# Digital_IO_Protection.net
KiCad netlist of a schematic drawn in Altium Designer
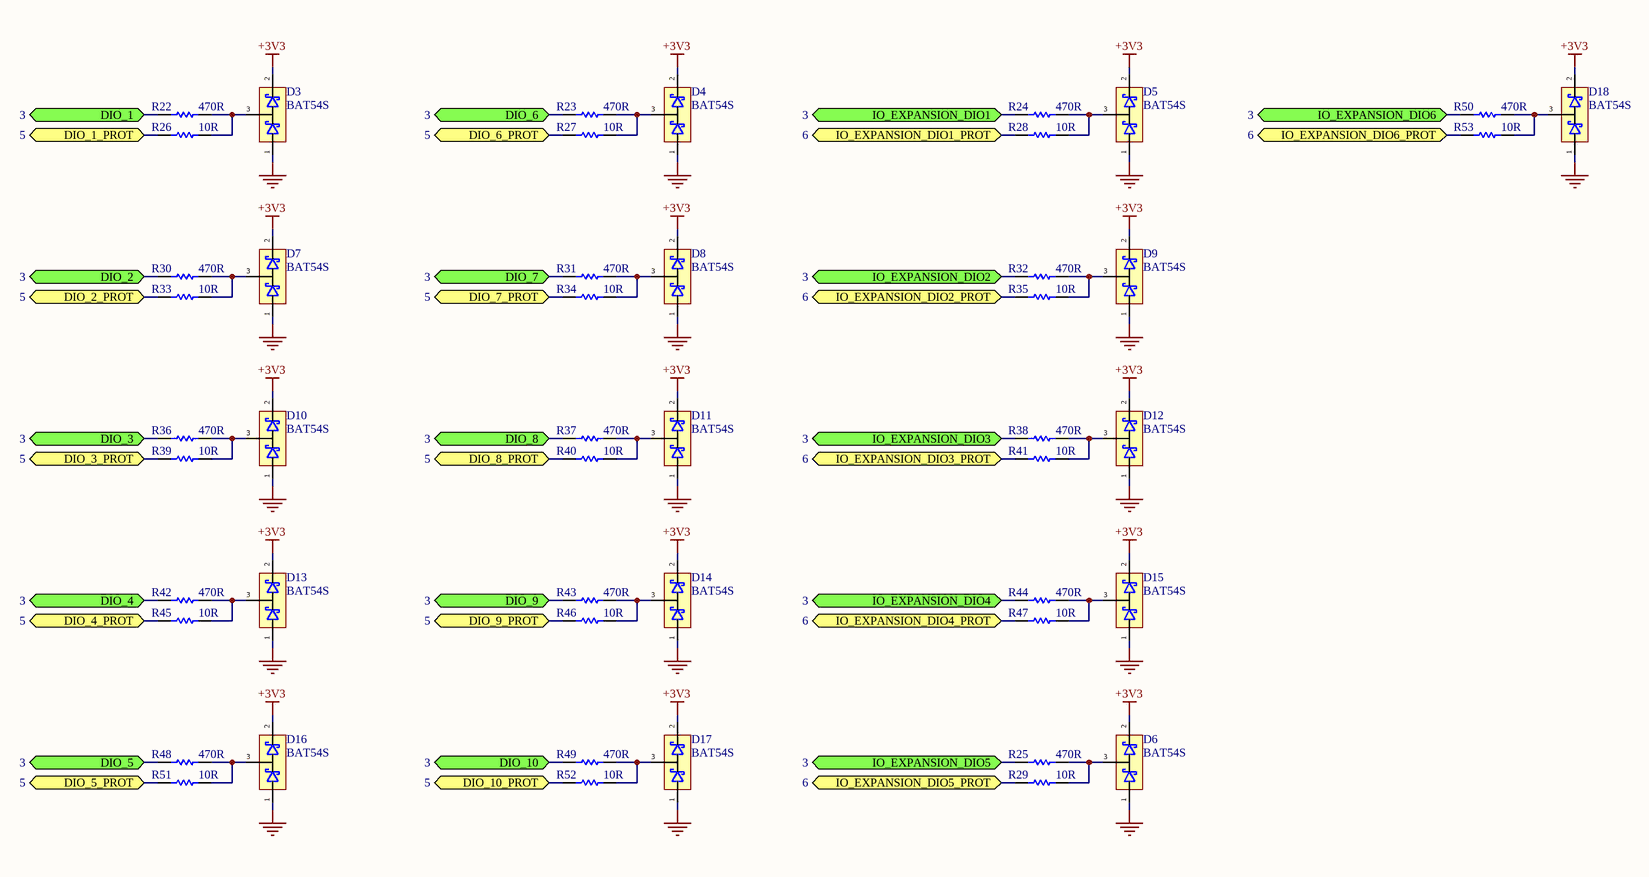
[diagram p0: Digital IO Protection.SchDoc]

(export (version "E")
  (design (tool "Eeschema 10.0.6"))
  (components
    (comp (ref "D3")
      (value "BAT54S")
      (footprint "SOT23-3")
      (description "Rectifier Diode Small Signal Schottky 40V 0.3A 5ns 3-Pin SOT-23 T/R")
      (fields
        (field (name "MANUFACTURER") "STMicroelectronics")
        (field (name "MANUFACTURER PART NUMBER") "BAT54SFILM")
      )
      (libsource (lib "MRT SCH Library") (part "Schottky Diode Array BAT54S"))
    )
    (comp (ref "D4")
      (value "BAT54S")
      (footprint "SOT23-3")
      (description "Rectifier Diode Small Signal Schottky 40V 0.3A 5ns 3-Pin SOT-23 T/R")
      (fields
        (field (name "MANUFACTURER") "STMicroelectronics")
        (field (name "MANUFACTURER PART NUMBER") "BAT54SFILM")
      )
      (libsource (lib "MRT SCH Library") (part "Schottky Diode Array BAT54S"))
    )
    (comp (ref "D5")
      (value "BAT54S")
      (footprint "SOT23-3")
      (description "Rectifier Diode Small Signal Schottky 40V 0.3A 5ns 3-Pin SOT-23 T/R")
      (fields
        (field (name "MANUFACTURER") "STMicroelectronics")
        (field (name "MANUFACTURER PART NUMBER") "BAT54SFILM")
      )
      (libsource (lib "MRT SCH Library") (part "Schottky Diode Array BAT54S"))
    )
    (comp (ref "D6")
      (value "BAT54S")
      (footprint "SOT23-3")
      (description "Rectifier Diode Small Signal Schottky 40V 0.3A 5ns 3-Pin SOT-23 T/R")
      (fields
        (field (name "MANUFACTURER") "STMicroelectronics")
        (field (name "MANUFACTURER PART NUMBER") "BAT54SFILM")
      )
      (libsource (lib "MRT SCH Library") (part "Schottky Diode Array BAT54S"))
    )
    (comp (ref "D7")
      (value "BAT54S")
      (footprint "SOT23-3")
      (description "Rectifier Diode Small Signal Schottky 40V 0.3A 5ns 3-Pin SOT-23 T/R")
      (fields
        (field (name "MANUFACTURER") "STMicroelectronics")
        (field (name "MANUFACTURER PART NUMBER") "BAT54SFILM")
      )
      (libsource (lib "MRT SCH Library") (part "Schottky Diode Array BAT54S"))
    )
    (comp (ref "D8")
      (value "BAT54S")
      (footprint "SOT23-3")
      (description "Rectifier Diode Small Signal Schottky 40V 0.3A 5ns 3-Pin SOT-23 T/R")
      (fields
        (field (name "MANUFACTURER") "STMicroelectronics")
        (field (name "MANUFACTURER PART NUMBER") "BAT54SFILM")
      )
      (libsource (lib "MRT SCH Library") (part "Schottky Diode Array BAT54S"))
    )
    (comp (ref "D9")
      (value "BAT54S")
      (footprint "SOT23-3")
      (description "Rectifier Diode Small Signal Schottky 40V 0.3A 5ns 3-Pin SOT-23 T/R")
      (fields
        (field (name "MANUFACTURER") "STMicroelectronics")
        (field (name "MANUFACTURER PART NUMBER") "BAT54SFILM")
      )
      (libsource (lib "MRT SCH Library") (part "Schottky Diode Array BAT54S"))
    )
    (comp (ref "D10")
      (value "BAT54S")
      (footprint "SOT23-3")
      (description "Rectifier Diode Small Signal Schottky 40V 0.3A 5ns 3-Pin SOT-23 T/R")
      (fields
        (field (name "MANUFACTURER") "STMicroelectronics")
        (field (name "MANUFACTURER PART NUMBER") "BAT54SFILM")
      )
      (libsource (lib "MRT SCH Library") (part "Schottky Diode Array BAT54S"))
    )
    (comp (ref "D11")
      (value "BAT54S")
      (footprint "SOT23-3")
      (description "Rectifier Diode Small Signal Schottky 40V 0.3A 5ns 3-Pin SOT-23 T/R")
      (fields
        (field (name "MANUFACTURER") "STMicroelectronics")
        (field (name "MANUFACTURER PART NUMBER") "BAT54SFILM")
      )
      (libsource (lib "MRT SCH Library") (part "Schottky Diode Array BAT54S"))
    )
    (comp (ref "D12")
      (value "BAT54S")
      (footprint "SOT23-3")
      (description "Rectifier Diode Small Signal Schottky 40V 0.3A 5ns 3-Pin SOT-23 T/R")
      (fields
        (field (name "MANUFACTURER") "STMicroelectronics")
        (field (name "MANUFACTURER PART NUMBER") "BAT54SFILM")
      )
      (libsource (lib "MRT SCH Library") (part "Schottky Diode Array BAT54S"))
    )
    (comp (ref "D13")
      (value "BAT54S")
      (footprint "SOT23-3")
      (description "Rectifier Diode Small Signal Schottky 40V 0.3A 5ns 3-Pin SOT-23 T/R")
      (fields
        (field (name "MANUFACTURER") "STMicroelectronics")
        (field (name "MANUFACTURER PART NUMBER") "BAT54SFILM")
      )
      (libsource (lib "MRT SCH Library") (part "Schottky Diode Array BAT54S"))
    )
    (comp (ref "D14")
      (value "BAT54S")
      (footprint "SOT23-3")
      (description "Rectifier Diode Small Signal Schottky 40V 0.3A 5ns 3-Pin SOT-23 T/R")
      (fields
        (field (name "MANUFACTURER") "STMicroelectronics")
        (field (name "MANUFACTURER PART NUMBER") "BAT54SFILM")
      )
      (libsource (lib "MRT SCH Library") (part "Schottky Diode Array BAT54S"))
    )
    (comp (ref "D15")
      (value "BAT54S")
      (footprint "SOT23-3")
      (description "Rectifier Diode Small Signal Schottky 40V 0.3A 5ns 3-Pin SOT-23 T/R")
      (fields
        (field (name "MANUFACTURER") "STMicroelectronics")
        (field (name "MANUFACTURER PART NUMBER") "BAT54SFILM")
      )
      (libsource (lib "MRT SCH Library") (part "Schottky Diode Array BAT54S"))
    )
    (comp (ref "D16")
      (value "BAT54S")
      (footprint "SOT23-3")
      (description "Rectifier Diode Small Signal Schottky 40V 0.3A 5ns 3-Pin SOT-23 T/R")
      (fields
        (field (name "MANUFACTURER") "STMicroelectronics")
        (field (name "MANUFACTURER PART NUMBER") "BAT54SFILM")
      )
      (libsource (lib "MRT SCH Library") (part "Schottky Diode Array BAT54S"))
    )
    (comp (ref "D17")
      (value "BAT54S")
      (footprint "SOT23-3")
      (description "Rectifier Diode Small Signal Schottky 40V 0.3A 5ns 3-Pin SOT-23 T/R")
      (fields
        (field (name "MANUFACTURER") "STMicroelectronics")
        (field (name "MANUFACTURER PART NUMBER") "BAT54SFILM")
      )
      (libsource (lib "MRT SCH Library") (part "Schottky Diode Array BAT54S"))
    )
    (comp (ref "D18")
      (value "BAT54S")
      (footprint "SOT23-3")
      (description "Rectifier Diode Small Signal Schottky 40V 0.3A 5ns 3-Pin SOT-23 T/R")
      (fields
        (field (name "MANUFACTURER") "STMicroelectronics")
        (field (name "MANUFACTURER PART NUMBER") "BAT54SFILM")
      )
      (libsource (lib "MRT SCH Library") (part "Schottky Diode Array BAT54S"))
    )
    (comp (ref "R22")
      (value "470R")
      (footprint "0805 RES")
      (fields (field (name "PUBLISHER") "Altium Limited"))
      (libsource (lib "Miscellaneous Devices") (part "Res1"))
    )
    (comp (ref "R23")
      (value "470R")
      (footprint "0805 RES")
      (fields (field (name "PUBLISHER") "Altium Limited"))
      (libsource (lib "Miscellaneous Devices") (part "Res1"))
    )
    (comp (ref "R24")
      (value "470R")
      (footprint "0805 RES")
      (fields (field (name "PUBLISHER") "Altium Limited"))
      (libsource (lib "Miscellaneous Devices") (part "Res1"))
    )
    (comp (ref "R25")
      (value "470R")
      (footprint "0805 RES")
      (fields (field (name "PUBLISHER") "Altium Limited"))
      (libsource (lib "Miscellaneous Devices") (part "Res1"))
    )
    (comp (ref "R26")
      (value "10R")
      (footprint "0603 RES")
      (fields (field (name "PUBLISHER") "Altium Limited"))
      (libsource (lib "Miscellaneous Devices") (part "Res1"))
    )
    (comp (ref "R27")
      (value "10R")
      (footprint "0603 RES")
      (fields (field (name "PUBLISHER") "Altium Limited"))
      (libsource (lib "Miscellaneous Devices") (part "Res1"))
    )
    (comp (ref "R28")
      (value "10R")
      (footprint "0603 RES")
      (fields (field (name "PUBLISHER") "Altium Limited"))
      (libsource (lib "Miscellaneous Devices") (part "Res1"))
    )
    (comp (ref "R29")
      (value "10R")
      (footprint "0603 RES")
      (fields (field (name "PUBLISHER") "Altium Limited"))
      (libsource (lib "Miscellaneous Devices") (part "Res1"))
    )
    (comp (ref "R30")
      (value "470R")
      (footprint "0805 RES")
      (fields (field (name "PUBLISHER") "Altium Limited"))
      (libsource (lib "Miscellaneous Devices") (part "Res1"))
    )
    (comp (ref "R31")
      (value "470R")
      (footprint "0805 RES")
      (fields (field (name "PUBLISHER") "Altium Limited"))
      (libsource (lib "Miscellaneous Devices") (part "Res1"))
    )
    (comp (ref "R32")
      (value "470R")
      (footprint "0805 RES")
      (fields (field (name "PUBLISHER") "Altium Limited"))
      (libsource (lib "Miscellaneous Devices") (part "Res1"))
    )
    (comp (ref "R33")
      (value "10R")
      (footprint "0603 RES")
      (fields (field (name "PUBLISHER") "Altium Limited"))
      (libsource (lib "Miscellaneous Devices") (part "Res1"))
    )
    (comp (ref "R34")
      (value "10R")
      (footprint "0603 RES")
      (fields (field (name "PUBLISHER") "Altium Limited"))
      (libsource (lib "Miscellaneous Devices") (part "Res1"))
    )
    (comp (ref "R35")
      (value "10R")
      (footprint "0603 RES")
      (fields (field (name "PUBLISHER") "Altium Limited"))
      (libsource (lib "Miscellaneous Devices") (part "Res1"))
    )
    (comp (ref "R36")
      (value "470R")
      (footprint "0805 RES")
      (fields (field (name "PUBLISHER") "Altium Limited"))
      (libsource (lib "Miscellaneous Devices") (part "Res1"))
    )
    (comp (ref "R37")
      (value "470R")
      (footprint "0805 RES")
      (fields (field (name "PUBLISHER") "Altium Limited"))
      (libsource (lib "Miscellaneous Devices") (part "Res1"))
    )
    (comp (ref "R38")
      (value "470R")
      (footprint "0805 RES")
      (fields (field (name "PUBLISHER") "Altium Limited"))
      (libsource (lib "Miscellaneous Devices") (part "Res1"))
    )
    (comp (ref "R39")
      (value "10R")
      (footprint "0603 RES")
      (fields (field (name "PUBLISHER") "Altium Limited"))
      (libsource (lib "Miscellaneous Devices") (part "Res1"))
    )
    (comp (ref "R40")
      (value "10R")
      (footprint "0603 RES")
      (fields (field (name "PUBLISHER") "Altium Limited"))
      (libsource (lib "Miscellaneous Devices") (part "Res1"))
    )
    (comp (ref "R41")
      (value "10R")
      (footprint "0603 RES")
      (fields (field (name "PUBLISHER") "Altium Limited"))
      (libsource (lib "Miscellaneous Devices") (part "Res1"))
    )
    (comp (ref "R42")
      (value "470R")
      (footprint "0805 RES")
      (fields (field (name "PUBLISHER") "Altium Limited"))
      (libsource (lib "Miscellaneous Devices") (part "Res1"))
    )
    (comp (ref "R43")
      (value "470R")
      (footprint "0805 RES")
      (fields (field (name "PUBLISHER") "Altium Limited"))
      (libsource (lib "Miscellaneous Devices") (part "Res1"))
    )
    (comp (ref "R44")
      (value "470R")
      (footprint "0805 RES")
      (fields (field (name "PUBLISHER") "Altium Limited"))
      (libsource (lib "Miscellaneous Devices") (part "Res1"))
    )
    (comp (ref "R45")
      (value "10R")
      (footprint "0603 RES")
      (fields (field (name "PUBLISHER") "Altium Limited"))
      (libsource (lib "Miscellaneous Devices") (part "Res1"))
    )
    (comp (ref "R46")
      (value "10R")
      (footprint "0603 RES")
      (fields (field (name "PUBLISHER") "Altium Limited"))
      (libsource (lib "Miscellaneous Devices") (part "Res1"))
    )
    (comp (ref "R47")
      (value "10R")
      (footprint "0603 RES")
      (fields (field (name "PUBLISHER") "Altium Limited"))
      (libsource (lib "Miscellaneous Devices") (part "Res1"))
    )
    (comp (ref "R48")
      (value "470R")
      (footprint "0805 RES")
      (fields (field (name "PUBLISHER") "Altium Limited"))
      (libsource (lib "Miscellaneous Devices") (part "Res1"))
    )
    (comp (ref "R49")
      (value "470R")
      (footprint "0805 RES")
      (fields (field (name "PUBLISHER") "Altium Limited"))
      (libsource (lib "Miscellaneous Devices") (part "Res1"))
    )
    (comp (ref "R50")
      (value "470R")
      (footprint "0805 RES")
      (fields (field (name "PUBLISHER") "Altium Limited"))
      (libsource (lib "Miscellaneous Devices") (part "Res1"))
    )
    (comp (ref "R51")
      (value "10R")
      (footprint "0603 RES")
      (fields (field (name "PUBLISHER") "Altium Limited"))
      (libsource (lib "Miscellaneous Devices") (part "Res1"))
    )
    (comp (ref "R52")
      (value "10R")
      (footprint "0603 RES")
      (fields (field (name "PUBLISHER") "Altium Limited"))
      (libsource (lib "Miscellaneous Devices") (part "Res1"))
    )
    (comp (ref "R53")
      (value "10R")
      (footprint "0603 RES")
      (fields (field (name "PUBLISHER") "Altium Limited"))
      (libsource (lib "Miscellaneous Devices") (part "Res1"))
    )
  )
  (nets
    (net (code "1") (name "+3V3") (class "Default")
      (node (ref "D10") (pin "2") (pinfunction "2_2") (pintype "passive"))
      (node (ref "D11") (pin "2") (pinfunction "2_2") (pintype "passive"))
      (node (ref "D12") (pin "2") (pinfunction "2_2") (pintype "passive"))
      (node (ref "D13") (pin "2") (pinfunction "2_2") (pintype "passive"))
      (node (ref "D14") (pin "2") (pinfunction "2_2") (pintype "passive"))
      (node (ref "D15") (pin "2") (pinfunction "2_2") (pintype "passive"))
      (node (ref "D16") (pin "2") (pinfunction "2_2") (pintype "passive"))
      (node (ref "D17") (pin "2") (pinfunction "2_2") (pintype "passive"))
      (node (ref "D18") (pin "2") (pinfunction "2_2") (pintype "passive"))
      (node (ref "D3") (pin "2") (pinfunction "2_2") (pintype "passive"))
      (node (ref "D4") (pin "2") (pinfunction "2_2") (pintype "passive"))
      (node (ref "D5") (pin "2") (pinfunction "2_2") (pintype "passive"))
      (node (ref "D6") (pin "2") (pinfunction "2_2") (pintype "passive"))
      (node (ref "D7") (pin "2") (pinfunction "2_2") (pintype "passive"))
      (node (ref "D8") (pin "2") (pinfunction "2_2") (pintype "passive"))
      (node (ref "D9") (pin "2") (pinfunction "2_2") (pintype "passive"))
    )
    (net (code "2") (name "/DIO_1") (class "Default")
      (node (ref "R22") (pin "1") (pinfunction "1_1") (pintype "passive"))
    )
    (net (code "3") (name "/DIO_1_PROT") (class "Default")
      (node (ref "R26") (pin "1") (pinfunction "1_1") (pintype "passive"))
    )
    (net (code "4") (name "/DIO_2") (class "Default")
      (node (ref "R30") (pin "1") (pinfunction "1_1") (pintype "passive"))
    )
    (net (code "5") (name "/DIO_2_PROT") (class "Default")
      (node (ref "R33") (pin "1") (pinfunction "1_1") (pintype "passive"))
    )
    (net (code "6") (name "/DIO_3") (class "Default")
      (node (ref "R36") (pin "1") (pinfunction "1_1") (pintype "passive"))
    )
    (net (code "7") (name "/DIO_3_PROT") (class "Default")
      (node (ref "R39") (pin "1") (pinfunction "1_1") (pintype "passive"))
    )
    (net (code "8") (name "/DIO_4") (class "Default")
      (node (ref "R42") (pin "1") (pinfunction "1_1") (pintype "passive"))
    )
    (net (code "9") (name "/DIO_4_PROT") (class "Default")
      (node (ref "R45") (pin "1") (pinfunction "1_1") (pintype "passive"))
    )
    (net (code "10") (name "/DIO_5") (class "Default")
      (node (ref "R48") (pin "1") (pinfunction "1_1") (pintype "passive"))
    )
    (net (code "11") (name "/DIO_5_PROT") (class "Default")
      (node (ref "R51") (pin "1") (pinfunction "1_1") (pintype "passive"))
    )
    (net (code "12") (name "/DIO_6") (class "Default")
      (node (ref "R23") (pin "1") (pinfunction "1_1") (pintype "passive"))
    )
    (net (code "13") (name "/DIO_6_PROT") (class "Default")
      (node (ref "R27") (pin "1") (pinfunction "1_1") (pintype "passive"))
    )
    (net (code "14") (name "/DIO_7") (class "Default")
      (node (ref "R31") (pin "1") (pinfunction "1_1") (pintype "passive"))
    )
    (net (code "15") (name "/DIO_7_PROT") (class "Default")
      (node (ref "R34") (pin "1") (pinfunction "1_1") (pintype "passive"))
    )
    (net (code "16") (name "/DIO_8") (class "Default")
      (node (ref "R37") (pin "1") (pinfunction "1_1") (pintype "passive"))
    )
    (net (code "17") (name "/DIO_8_PROT") (class "Default")
      (node (ref "R40") (pin "1") (pinfunction "1_1") (pintype "passive"))
    )
    (net (code "18") (name "/DIO_9") (class "Default")
      (node (ref "R43") (pin "1") (pinfunction "1_1") (pintype "passive"))
    )
    (net (code "19") (name "/DIO_9_PROT") (class "Default")
      (node (ref "R46") (pin "1") (pinfunction "1_1") (pintype "passive"))
    )
    (net (code "20") (name "/DIO_10") (class "Default")
      (node (ref "R49") (pin "1") (pinfunction "1_1") (pintype "passive"))
    )
    (net (code "21") (name "/DIO_10_PROT") (class "Default")
      (node (ref "R52") (pin "1") (pinfunction "1_1") (pintype "passive"))
    )
    (net (code "22") (name "/IO_EXPANSION_DIO1") (class "Default")
      (node (ref "R24") (pin "1") (pinfunction "1_1") (pintype "passive"))
    )
    (net (code "23") (name "/IO_EXPANSION_DIO1_PROT") (class "Default")
      (node (ref "R28") (pin "1") (pinfunction "1_1") (pintype "passive"))
    )
    (net (code "24") (name "/IO_EXPANSION_DIO2") (class "Default")
      (node (ref "R32") (pin "1") (pinfunction "1_1") (pintype "passive"))
    )
    (net (code "25") (name "/IO_EXPANSION_DIO2_PROT") (class "Default")
      (node (ref "R35") (pin "1") (pinfunction "1_1") (pintype "passive"))
    )
    (net (code "26") (name "/IO_EXPANSION_DIO3") (class "Default")
      (node (ref "R38") (pin "1") (pinfunction "1_1") (pintype "passive"))
    )
    (net (code "27") (name "/IO_EXPANSION_DIO3_PROT") (class "Default")
      (node (ref "R41") (pin "1") (pinfunction "1_1") (pintype "passive"))
    )
    (net (code "28") (name "/IO_EXPANSION_DIO4") (class "Default")
      (node (ref "R44") (pin "1") (pinfunction "1_1") (pintype "passive"))
    )
    (net (code "29") (name "/IO_EXPANSION_DIO4_PROT") (class "Default")
      (node (ref "R47") (pin "1") (pinfunction "1_1") (pintype "passive"))
    )
    (net (code "30") (name "/IO_EXPANSION_DIO5") (class "Default")
      (node (ref "R25") (pin "1") (pinfunction "1_1") (pintype "passive"))
    )
    (net (code "31") (name "/IO_EXPANSION_DIO5_PROT") (class "Default")
      (node (ref "R29") (pin "1") (pinfunction "1_1") (pintype "passive"))
    )
    (net (code "32") (name "/IO_EXPANSION_DIO6") (class "Default")
      (node (ref "R50") (pin "1") (pinfunction "1_1") (pintype "passive"))
    )
    (net (code "33") (name "/IO_EXPANSION_DIO6_PROT") (class "Default")
      (node (ref "R53") (pin "1") (pinfunction "1_1") (pintype "passive"))
    )
    (net (code "34") (name "GND") (class "Default")
      (node (ref "D10") (pin "1") (pinfunction "1_1") (pintype "passive"))
      (node (ref "D11") (pin "1") (pinfunction "1_1") (pintype "passive"))
      (node (ref "D12") (pin "1") (pinfunction "1_1") (pintype "passive"))
      (node (ref "D13") (pin "1") (pinfunction "1_1") (pintype "passive"))
      (node (ref "D14") (pin "1") (pinfunction "1_1") (pintype "passive"))
      (node (ref "D15") (pin "1") (pinfunction "1_1") (pintype "passive"))
      (node (ref "D16") (pin "1") (pinfunction "1_1") (pintype "passive"))
      (node (ref "D17") (pin "1") (pinfunction "1_1") (pintype "passive"))
      (node (ref "D18") (pin "1") (pinfunction "1_1") (pintype "passive"))
      (node (ref "D3") (pin "1") (pinfunction "1_1") (pintype "passive"))
      (node (ref "D4") (pin "1") (pinfunction "1_1") (pintype "passive"))
      (node (ref "D5") (pin "1") (pinfunction "1_1") (pintype "passive"))
      (node (ref "D6") (pin "1") (pinfunction "1_1") (pintype "passive"))
      (node (ref "D7") (pin "1") (pinfunction "1_1") (pintype "passive"))
      (node (ref "D8") (pin "1") (pinfunction "1_1") (pintype "passive"))
      (node (ref "D9") (pin "1") (pinfunction "1_1") (pintype "passive"))
    )
    (net (code "35") (name "Net-(D3-Pad3)") (class "Default")
      (node (ref "D3") (pin "3") (pinfunction "3_3") (pintype "passive"))
      (node (ref "R22") (pin "2") (pinfunction "2_2") (pintype "passive"))
      (node (ref "R26") (pin "2") (pinfunction "2_2") (pintype "passive"))
    )
    (net (code "36") (name "Net-(D4-Pad3)") (class "Default")
      (node (ref "D4") (pin "3") (pinfunction "3_3") (pintype "passive"))
      (node (ref "R23") (pin "2") (pinfunction "2_2") (pintype "passive"))
      (node (ref "R27") (pin "2") (pinfunction "2_2") (pintype "passive"))
    )
    (net (code "37") (name "Net-(D5-Pad3)") (class "Default")
      (node (ref "D5") (pin "3") (pinfunction "3_3") (pintype "passive"))
      (node (ref "R24") (pin "2") (pinfunction "2_2") (pintype "passive"))
      (node (ref "R28") (pin "2") (pinfunction "2_2") (pintype "passive"))
    )
    (net (code "38") (name "Net-(D6-Pad3)") (class "Default")
      (node (ref "D6") (pin "3") (pinfunction "3_3") (pintype "passive"))
      (node (ref "R25") (pin "2") (pinfunction "2_2") (pintype "passive"))
      (node (ref "R29") (pin "2") (pinfunction "2_2") (pintype "passive"))
    )
    (net (code "39") (name "Net-(D7-Pad3)") (class "Default")
      (node (ref "D7") (pin "3") (pinfunction "3_3") (pintype "passive"))
      (node (ref "R30") (pin "2") (pinfunction "2_2") (pintype "passive"))
      (node (ref "R33") (pin "2") (pinfunction "2_2") (pintype "passive"))
    )
    (net (code "40") (name "Net-(D8-Pad3)") (class "Default")
      (node (ref "D8") (pin "3") (pinfunction "3_3") (pintype "passive"))
      (node (ref "R31") (pin "2") (pinfunction "2_2") (pintype "passive"))
      (node (ref "R34") (pin "2") (pinfunction "2_2") (pintype "passive"))
    )
    (net (code "41") (name "Net-(D9-Pad3)") (class "Default")
      (node (ref "D9") (pin "3") (pinfunction "3_3") (pintype "passive"))
      (node (ref "R32") (pin "2") (pinfunction "2_2") (pintype "passive"))
      (node (ref "R35") (pin "2") (pinfunction "2_2") (pintype "passive"))
    )
    (net (code "42") (name "Net-(D10-Pad3)") (class "Default")
      (node (ref "D10") (pin "3") (pinfunction "3_3") (pintype "passive"))
      (node (ref "R36") (pin "2") (pinfunction "2_2") (pintype "passive"))
      (node (ref "R39") (pin "2") (pinfunction "2_2") (pintype "passive"))
    )
    (net (code "43") (name "Net-(D11-Pad3)") (class "Default")
      (node (ref "D11") (pin "3") (pinfunction "3_3") (pintype "passive"))
      (node (ref "R37") (pin "2") (pinfunction "2_2") (pintype "passive"))
      (node (ref "R40") (pin "2") (pinfunction "2_2") (pintype "passive"))
    )
    (net (code "44") (name "Net-(D12-Pad3)") (class "Default")
      (node (ref "D12") (pin "3") (pinfunction "3_3") (pintype "passive"))
      (node (ref "R38") (pin "2") (pinfunction "2_2") (pintype "passive"))
      (node (ref "R41") (pin "2") (pinfunction "2_2") (pintype "passive"))
    )
    (net (code "45") (name "Net-(D13-Pad3)") (class "Default")
      (node (ref "D13") (pin "3") (pinfunction "3_3") (pintype "passive"))
      (node (ref "R42") (pin "2") (pinfunction "2_2") (pintype "passive"))
      (node (ref "R45") (pin "2") (pinfunction "2_2") (pintype "passive"))
    )
    (net (code "46") (name "Net-(D14-Pad3)") (class "Default")
      (node (ref "D14") (pin "3") (pinfunction "3_3") (pintype "passive"))
      (node (ref "R43") (pin "2") (pinfunction "2_2") (pintype "passive"))
      (node (ref "R46") (pin "2") (pinfunction "2_2") (pintype "passive"))
    )
    (net (code "47") (name "Net-(D15-Pad3)") (class "Default")
      (node (ref "D15") (pin "3") (pinfunction "3_3") (pintype "passive"))
      (node (ref "R44") (pin "2") (pinfunction "2_2") (pintype "passive"))
      (node (ref "R47") (pin "2") (pinfunction "2_2") (pintype "passive"))
    )
    (net (code "48") (name "Net-(D16-Pad3)") (class "Default")
      (node (ref "D16") (pin "3") (pinfunction "3_3") (pintype "passive"))
      (node (ref "R48") (pin "2") (pinfunction "2_2") (pintype "passive"))
      (node (ref "R51") (pin "2") (pinfunction "2_2") (pintype "passive"))
    )
    (net (code "49") (name "Net-(D17-Pad3)") (class "Default")
      (node (ref "D17") (pin "3") (pinfunction "3_3") (pintype "passive"))
      (node (ref "R49") (pin "2") (pinfunction "2_2") (pintype "passive"))
      (node (ref "R52") (pin "2") (pinfunction "2_2") (pintype "passive"))
    )
    (net (code "50") (name "Net-(D18-Pad3)") (class "Default")
      (node (ref "D18") (pin "3") (pinfunction "3_3") (pintype "passive"))
      (node (ref "R50") (pin "2") (pinfunction "2_2") (pintype "passive"))
      (node (ref "R53") (pin "2") (pinfunction "2_2") (pintype "passive"))
    )
  )
)
